# Open_Lamborghino.net
KiCad netlist of a schematic drawn in EAGLE
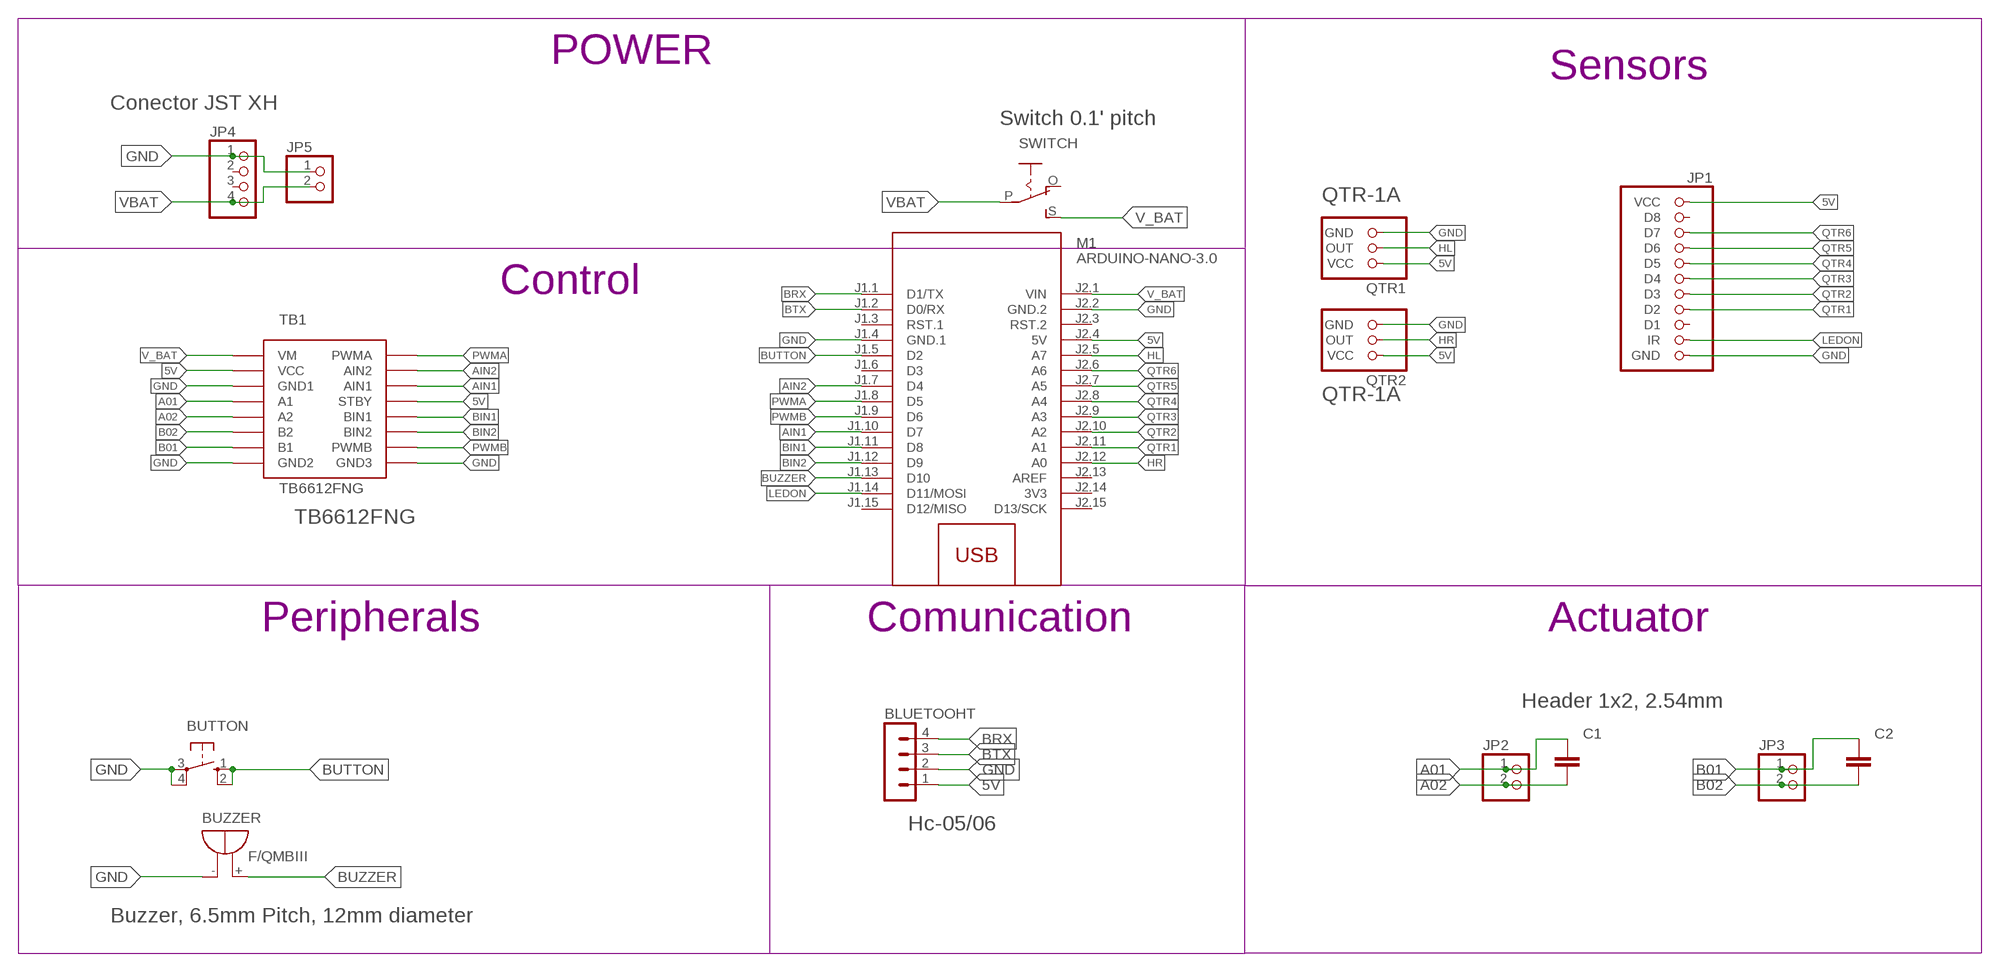
[diagram p0: schematic, sheet 1]

(export (version "E")
  (design (tool "Eeschema 10.0.6"))
  (components
    (comp (ref "BLUETOOHT")
      (value "MA04-1")
      (footprint "eagle-import:MA04-1")
      (libsource (lib "eagle-import") (part "MA04-1"))
    )
    (comp (ref "BUTTON")
      (value "10-XX")
      (footprint "eagle-import:B3F-10XX")
      (fields (field (name "MPN") "B3F-1000"))
      (libsource (lib "eagle-import") (part "10-XX"))
    )
    (comp (ref "BUZZER")
      (value "F/QMBIII")
      (footprint "eagle-import:F_QMBIII")
      (libsource (lib "eagle-import") (part "F/QMBIII"))
    )
    (comp (ref "C1")
      (value "C_CHIP-1206(3216-METRIC)")
      (footprint "eagle-import:CAPC3216X135")
      (libsource (lib "eagle-import") (part "CCHIP-1206(3216-METRIC)_"))
    )
    (comp (ref "C2")
      (value "C_CHIP-1206(3216-METRIC)")
      (footprint "eagle-import:CAPC3216X135")
      (libsource (lib "eagle-import") (part "CCHIP-1206(3216-METRIC)_"))
    )
    (comp (ref "JP1")
      (value "QTR8A(CHINO)")
      (footprint "eagle-import:1X11")
      (libsource (lib "eagle-import") (part "QTR8A(CHINO)"))
    )
    (comp (ref "JP2")
      (value "PINHD-1X2")
      (footprint "eagle-import:1X02")
      (libsource (lib "eagle-import") (part "PINHD-1X2"))
    )
    (comp (ref "JP3")
      (value "PINHD-1X2")
      (footprint "eagle-import:1X02")
      (libsource (lib "eagle-import") (part "PINHD-1X2"))
    )
    (comp (ref "JP4")
      (value "PINHD-1X4")
      (footprint "eagle-import:1X04")
      (libsource (lib "eagle-import") (part "PINHD-1X4"))
    )
    (comp (ref "JP5")
      (value "PINHD-1X2")
      (footprint "eagle-import:1X02")
      (libsource (lib "eagle-import") (part "PINHD-1X2"))
    )
    (comp (ref "M1")
      (value "ARDUINO-NANO-3.0")
      (footprint "eagle-import:ARDUINO-NANO-3.0")
      (libsource (lib "eagle-import") (part "ARDUINO-NANO-3.0"))
    )
    (comp (ref "QTR1")
      (value "QTR1(CHINO)")
      (footprint "eagle-import:QTR1")
      (libsource (lib "eagle-import") (part "QTR1(CHINO)"))
    )
    (comp (ref "QTR2")
      (value "QTR1(CHINO)")
      (footprint "eagle-import:QTR1")
      (libsource (lib "eagle-import") (part "QTR1(CHINO)"))
    )
    (comp (ref "SWITCH")
      (value "EG1218S")
      (footprint "eagle-import:EG1218")
      (libsource (lib "eagle-import") (part "EG1218S"))
    )
    (comp (ref "TB1")
      (value "TB6612FNG")
      (footprint "eagle-import:TB6612FNG")
      (libsource (lib "eagle-import") (part "TB6612FNG"))
    )
  )
  (nets
    (net (code "1") (name "/3V3") (class "Default")
      (node (ref "M1") (pin "J2.14") (pinfunction "3V3_J2.14") (pintype "power_in"))
    )
    (net (code "2") (name "5V") (class "Default")
      (node (ref "BLUETOOHT") (pin "1") (pinfunction "1_1") (pintype "passive"))
      (node (ref "JP1") (pin "1") (pinfunction "VCC_1") (pintype "passive"))
      (node (ref "M1") (pin "J2.4") (pinfunction "5V_J2.4") (pintype "power_in"))
      (node (ref "QTR1") (pin "1") (pinfunction "VCC_1") (pintype "power_in"))
      (node (ref "QTR2") (pin "1") (pinfunction "VCC_1") (pintype "power_in"))
      (node (ref "TB1") (pin "STBY") (pinfunction "STBY_STBY") (pintype "bidirectional"))
      (node (ref "TB1") (pin "VCC") (pinfunction "VCC_VCC") (pintype "bidirectional"))
    )
    (net (code "3") (name "A01") (class "Default")
      (node (ref "C1") (pin "1") (pinfunction "1_1") (pintype "passive"))
      (node (ref "JP2") (pin "1") (pinfunction "1_1") (pintype "passive"))
      (node (ref "TB1") (pin "A1") (pinfunction "A1_A1") (pintype "bidirectional"))
    )
    (net (code "4") (name "A02") (class "Default")
      (node (ref "C1") (pin "2") (pinfunction "2_2") (pintype "passive"))
      (node (ref "JP2") (pin "2") (pinfunction "2_2") (pintype "passive"))
      (node (ref "TB1") (pin "A2") (pinfunction "A2_A2") (pintype "bidirectional"))
    )
    (net (code "5") (name "AIN1") (class "Default")
      (node (ref "M1") (pin "J1.10") (pinfunction "D7_J1.10") (pintype "bidirectional"))
      (node (ref "TB1") (pin "AIN1") (pinfunction "AIN1_AIN1") (pintype "bidirectional"))
    )
    (net (code "6") (name "AIN2") (class "Default")
      (node (ref "M1") (pin "J1.7") (pinfunction "D4_J1.7") (pintype "bidirectional"))
      (node (ref "TB1") (pin "AIN2") (pinfunction "AIN2_AIN2") (pintype "bidirectional"))
    )
    (net (code "7") (name "B01") (class "Default")
      (node (ref "C2") (pin "1") (pinfunction "1_1") (pintype "passive"))
      (node (ref "JP3") (pin "1") (pinfunction "1_1") (pintype "passive"))
      (node (ref "TB1") (pin "B1") (pinfunction "B1_B1") (pintype "bidirectional"))
    )
    (net (code "8") (name "B02") (class "Default")
      (node (ref "C2") (pin "2") (pinfunction "2_2") (pintype "passive"))
      (node (ref "JP3") (pin "2") (pinfunction "2_2") (pintype "passive"))
      (node (ref "TB1") (pin "B2") (pinfunction "B2_B2") (pintype "bidirectional"))
    )
    (net (code "9") (name "BIN1") (class "Default")
      (node (ref "M1") (pin "J1.11") (pinfunction "D8_J1.11") (pintype "bidirectional"))
      (node (ref "TB1") (pin "BIN1") (pinfunction "BIN1_BIN1") (pintype "bidirectional"))
    )
    (net (code "10") (name "BIN2") (class "Default")
      (node (ref "M1") (pin "J1.12") (pinfunction "D9_J1.12") (pintype "bidirectional"))
      (node (ref "TB1") (pin "BIN2") (pinfunction "BIN2_BIN2") (pintype "bidirectional"))
    )
    (net (code "11") (name "BRX") (class "Default")
      (node (ref "BLUETOOHT") (pin "4") (pinfunction "4_4") (pintype "passive"))
      (node (ref "M1") (pin "J1.1") (pinfunction "D1/TX_J1.1") (pintype "bidirectional"))
    )
    (net (code "12") (name "BTX") (class "Default")
      (node (ref "BLUETOOHT") (pin "3") (pinfunction "3_3") (pintype "passive"))
      (node (ref "M1") (pin "J1.2") (pinfunction "D0/RX_J1.2") (pintype "bidirectional"))
    )
    (net (code "13") (name "BUTTON") (class "Default")
      (node (ref "BUTTON") (pin "1") (pinfunction "S_1") (pintype "passive"))
      (node (ref "BUTTON") (pin "2") (pinfunction "S1_2") (pintype "passive"))
      (node (ref "M1") (pin "J1.5") (pinfunction "D2_J1.5") (pintype "bidirectional"))
    )
    (net (code "14") (name "BUZZER") (class "Default")
      (node (ref "BUZZER") (pin "+") (pinfunction "-_+") (pintype "passive"))
      (node (ref "M1") (pin "J1.13") (pinfunction "D10_J1.13") (pintype "bidirectional"))
    )
    (net (code "15") (name "GND") (class "Default")
      (node (ref "BLUETOOHT") (pin "2") (pinfunction "2_2") (pintype "passive"))
      (node (ref "BUTTON") (pin "3") (pinfunction "P_3") (pintype "passive"))
      (node (ref "BUTTON") (pin "4") (pinfunction "P1_4") (pintype "passive"))
      (node (ref "BUZZER") (pin "-") (pinfunction "+_-") (pintype "passive"))
      (node (ref "JP1") (pin "11") (pinfunction "GND_11") (pintype "passive"))
      (node (ref "JP4") (pin "1") (pinfunction "1_1") (pintype "passive"))
      (node (ref "JP5") (pin "1") (pinfunction "1_1") (pintype "passive"))
      (node (ref "M1") (pin "J1.4") (pinfunction "GND.1_J1.4") (pintype "power_in"))
      (node (ref "M1") (pin "J2.2") (pinfunction "GND.2_J2.2") (pintype "power_in"))
      (node (ref "QTR1") (pin "3") (pinfunction "GND_3") (pintype "power_in"))
      (node (ref "QTR2") (pin "3") (pinfunction "GND_3") (pintype "power_in"))
      (node (ref "TB1") (pin "GND1") (pinfunction "GND1_GND1") (pintype "bidirectional"))
      (node (ref "TB1") (pin "GND2") (pinfunction "GND2_GND2") (pintype "bidirectional"))
      (node (ref "TB1") (pin "GND3") (pinfunction "GND3_GND3") (pintype "bidirectional"))
    )
    (net (code "16") (name "HL") (class "Default")
      (node (ref "M1") (pin "J2.5") (pinfunction "A7_J2.5") (pintype "bidirectional"))
      (node (ref "QTR1") (pin "2") (pinfunction "OUT_2") (pintype "output"))
    )
    (net (code "17") (name "HR") (class "Default")
      (node (ref "M1") (pin "J2.12") (pinfunction "A0_J2.12") (pintype "bidirectional"))
      (node (ref "QTR2") (pin "2") (pinfunction "OUT_2") (pintype "output"))
    )
    (net (code "18") (name "LEDON") (class "Default")
      (node (ref "JP1") (pin "10") (pinfunction "IR_10") (pintype "passive"))
      (node (ref "M1") (pin "J1.14") (pinfunction "D11/MOSI_J1.14") (pintype "bidirectional"))
    )
    (net (code "19") (name "PWMA") (class "Default")
      (node (ref "M1") (pin "J1.8") (pinfunction "D5_J1.8") (pintype "bidirectional"))
      (node (ref "TB1") (pin "PWMA") (pinfunction "PWMA_PWMA") (pintype "bidirectional"))
    )
    (net (code "20") (name "PWMB") (class "Default")
      (node (ref "M1") (pin "J1.9") (pinfunction "D6_J1.9") (pintype "bidirectional"))
      (node (ref "TB1") (pin "PWMB") (pinfunction "PWMB_PWMB") (pintype "bidirectional"))
    )
    (net (code "21") (name "QTR1") (class "Default")
      (node (ref "JP1") (pin "8") (pinfunction "D2_8") (pintype "passive"))
      (node (ref "M1") (pin "J2.11") (pinfunction "A1_J2.11") (pintype "bidirectional"))
    )
    (net (code "22") (name "QTR2") (class "Default")
      (node (ref "JP1") (pin "7") (pinfunction "D3_7") (pintype "passive"))
      (node (ref "M1") (pin "J2.10") (pinfunction "A2_J2.10") (pintype "bidirectional"))
    )
    (net (code "23") (name "QTR3") (class "Default")
      (node (ref "JP1") (pin "6") (pinfunction "D4_6") (pintype "passive"))
      (node (ref "M1") (pin "J2.9") (pinfunction "A3_J2.9") (pintype "bidirectional"))
    )
    (net (code "24") (name "QTR4") (class "Default")
      (node (ref "JP1") (pin "5") (pinfunction "D5_5") (pintype "passive"))
      (node (ref "M1") (pin "J2.8") (pinfunction "A4_J2.8") (pintype "bidirectional"))
    )
    (net (code "25") (name "QTR5") (class "Default")
      (node (ref "JP1") (pin "4") (pinfunction "D6_4") (pintype "passive"))
      (node (ref "M1") (pin "J2.7") (pinfunction "A5_J2.7") (pintype "bidirectional"))
    )
    (net (code "26") (name "QTR6") (class "Default")
      (node (ref "JP1") (pin "3") (pinfunction "D7_3") (pintype "passive"))
      (node (ref "M1") (pin "J2.6") (pinfunction "A6_J2.6") (pintype "bidirectional"))
    )
    (net (code "27") (name "VBAT") (class "Default")
      (node (ref "JP4") (pin "4") (pinfunction "4_4") (pintype "passive"))
      (node (ref "JP5") (pin "2") (pinfunction "2_2") (pintype "passive"))
      (node (ref "SWITCH") (pin "P") (pinfunction "P_P") (pintype "passive"))
    )
    (net (code "28") (name "V_BAT") (class "Default")
      (node (ref "M1") (pin "J2.1") (pinfunction "VIN_J2.1") (pintype "power_in"))
      (node (ref "SWITCH") (pin "S") (pinfunction "S_S") (pintype "passive"))
      (node (ref "TB1") (pin "VM") (pinfunction "VM_VM") (pintype "bidirectional"))
    )
    (net (code "29") (name "unconnected-(JP1-D1-Pad9)") (class "Default")
      (node (ref "JP1") (pin "9") (pinfunction "D1_9") (pintype "passive"))
    )
    (net (code "30") (name "unconnected-(JP1-D8-Pad2)") (class "Default")
      (node (ref "JP1") (pin "2") (pinfunction "D8_2") (pintype "passive"))
    )
    (net (code "31") (name "unconnected-(JP4-Pad2)") (class "Default")
      (node (ref "JP4") (pin "2") (pinfunction "2_2") (pintype "passive"))
    )
    (net (code "32") (name "unconnected-(JP4-Pad3)") (class "Default")
      (node (ref "JP4") (pin "3") (pinfunction "3_3") (pintype "passive"))
    )
    (net (code "33") (name "unconnected-(M1-AREF-PadJ2.13)") (class "Default")
      (node (ref "M1") (pin "J2.13") (pinfunction "AREF_J2.13") (pintype "bidirectional"))
    )
    (net (code "34") (name "unconnected-(M1-D3-PadJ1.6)") (class "Default")
      (node (ref "M1") (pin "J1.6") (pinfunction "D3_J1.6") (pintype "bidirectional"))
    )
    (net (code "35") (name "unconnected-(M1-D12{slash}MISO-PadJ1.15)") (class "Default")
      (node (ref "M1") (pin "J1.15") (pinfunction "D12/MISO_J1.15") (pintype "bidirectional"))
    )
    (net (code "36") (name "unconnected-(M1-D13{slash}SCK-PadJ2.15)") (class "Default")
      (node (ref "M1") (pin "J2.15") (pinfunction "D13/SCK_J2.15") (pintype "bidirectional"))
    )
    (net (code "37") (name "unconnected-(M1-RST.1-PadJ1.3)") (class "Default")
      (node (ref "M1") (pin "J1.3") (pinfunction "RST.1_J1.3") (pintype "bidirectional"))
    )
    (net (code "38") (name "unconnected-(M1-RST.2-PadJ2.3)") (class "Default")
      (node (ref "M1") (pin "J2.3") (pinfunction "RST.2_J2.3") (pintype "bidirectional"))
    )
    (net (code "39") (name "unconnected-(SWITCH-PadO)") (class "Default")
      (node (ref "SWITCH") (pin "O") (pinfunction "O_O") (pintype "passive"))
    )
  )
)
